# Sensors_v1_0.net
KiCad netlist of a schematic drawn in EAGLE
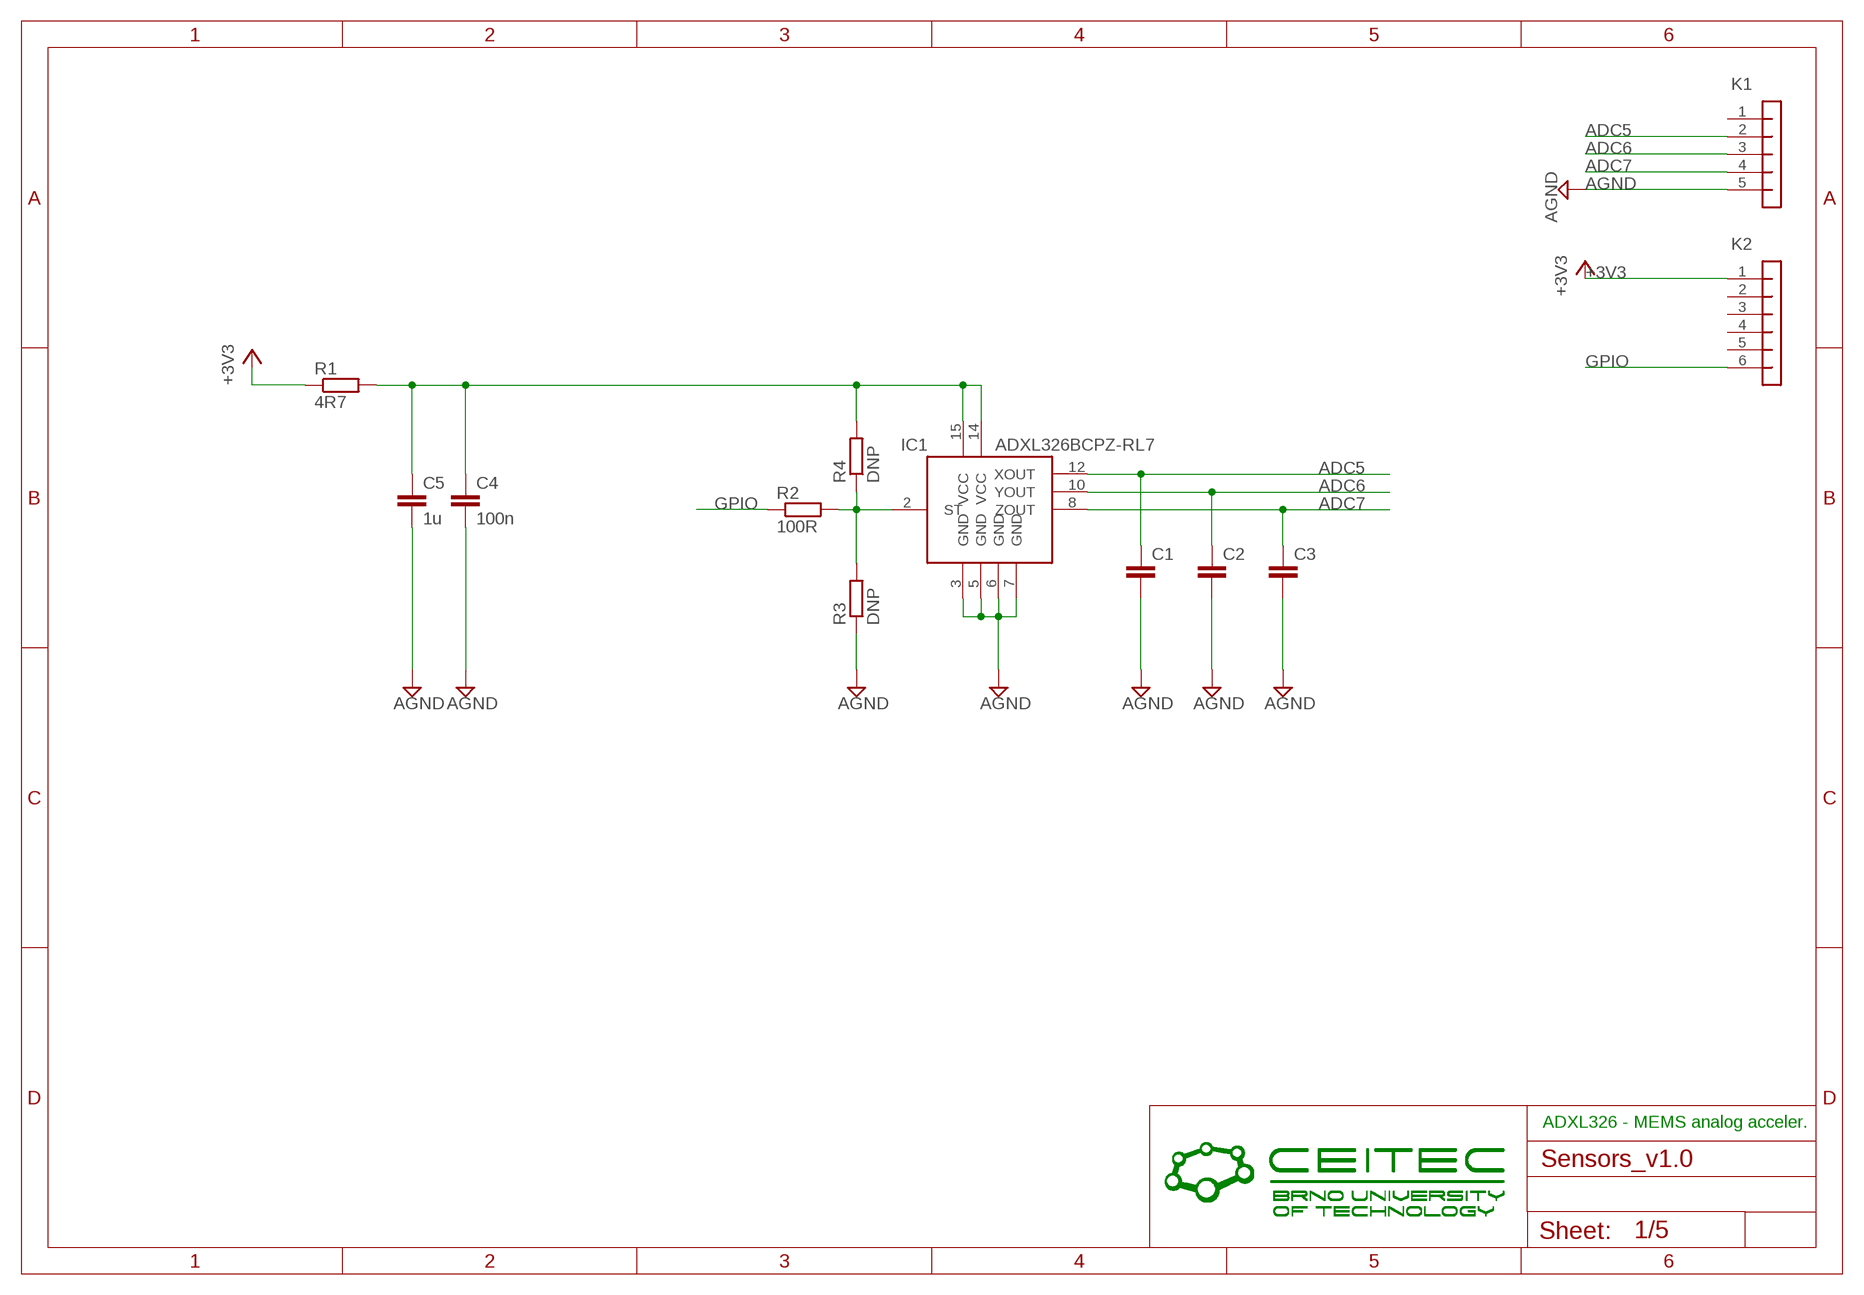
[diagram p0: schematic, sheet 1]
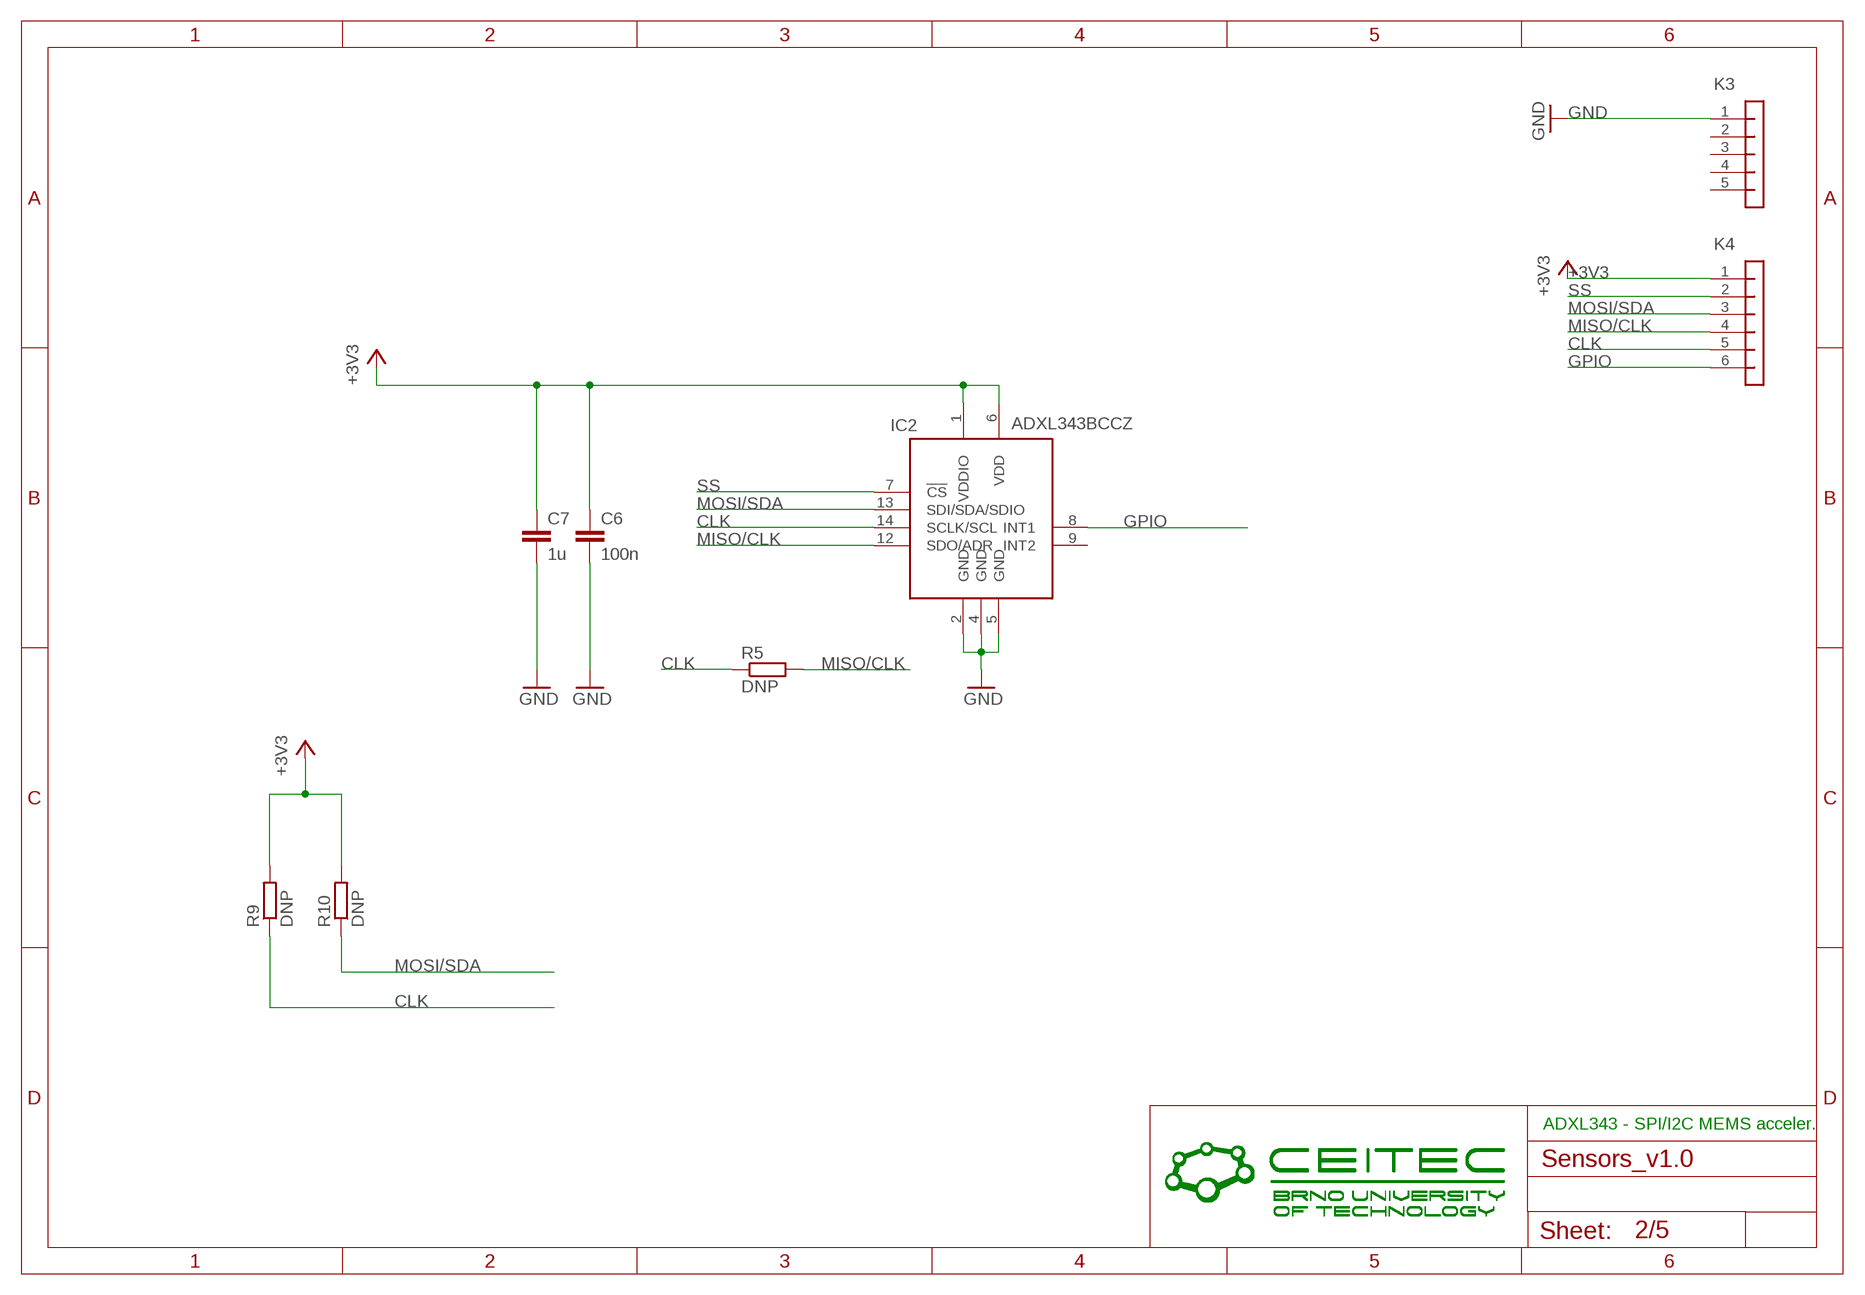
[diagram p1: schematic, sheet 2]
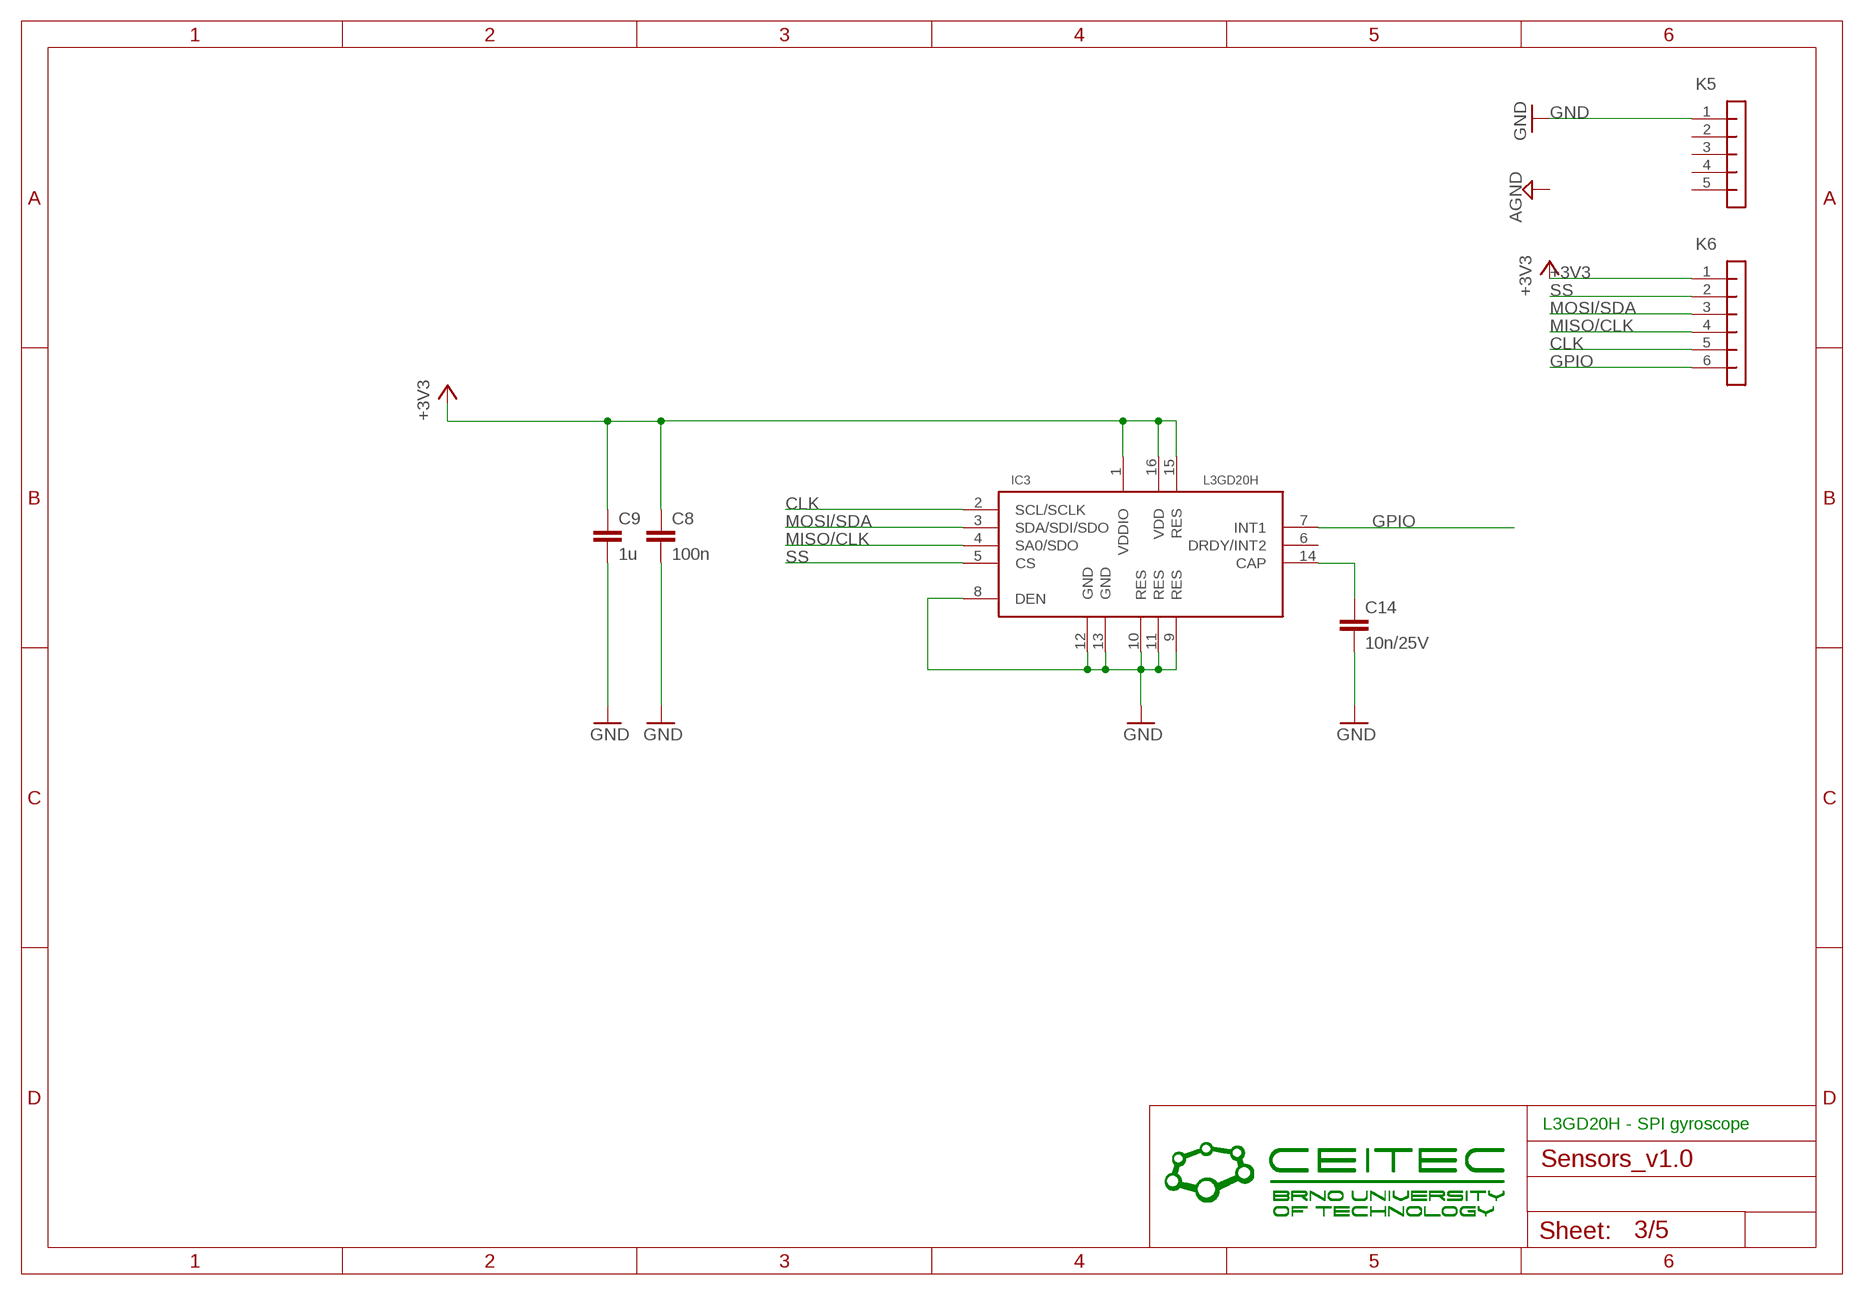
[diagram p2: schematic, sheet 3]
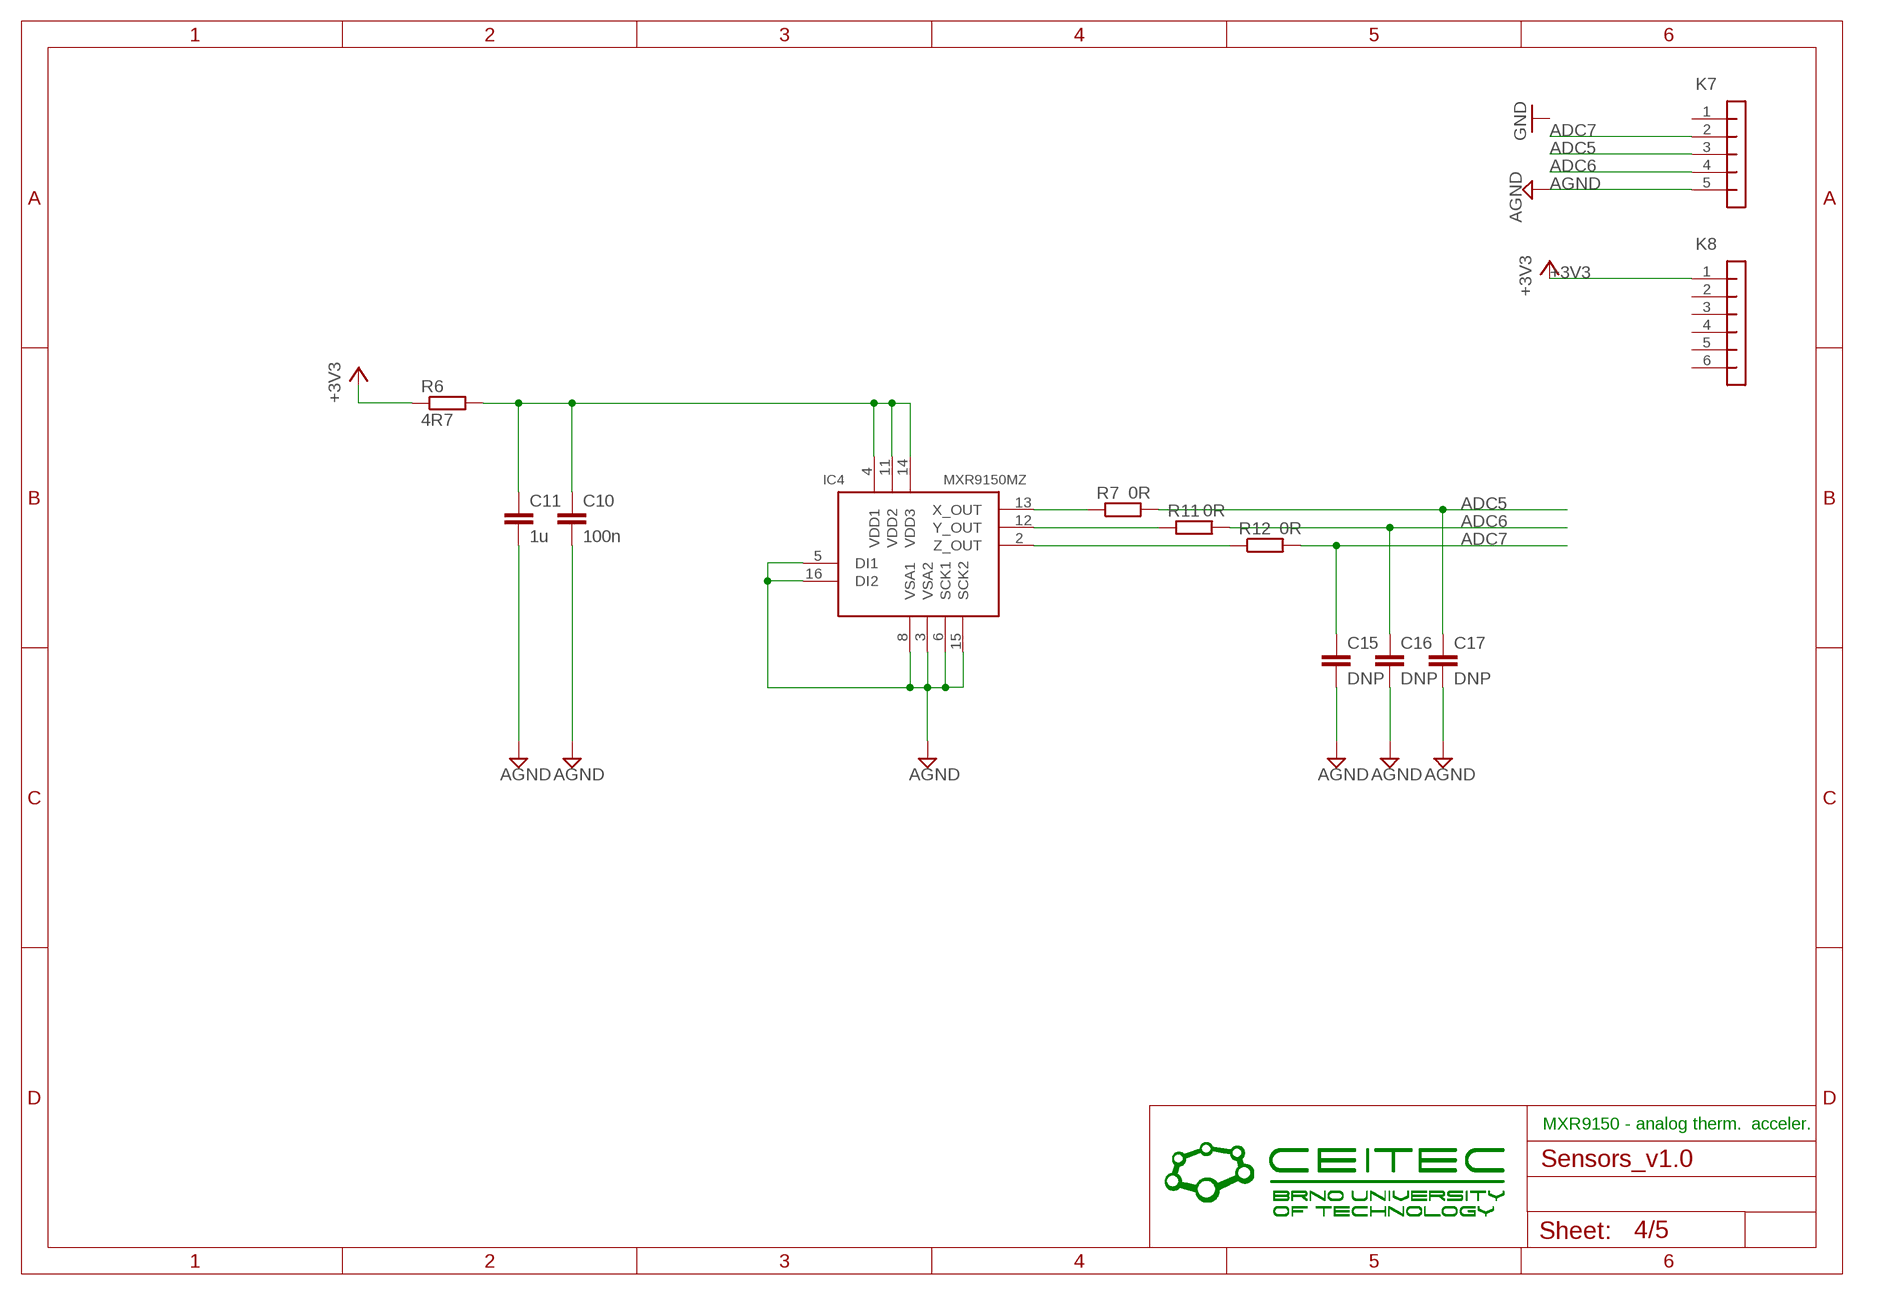
[diagram p3: schematic, sheet 4]
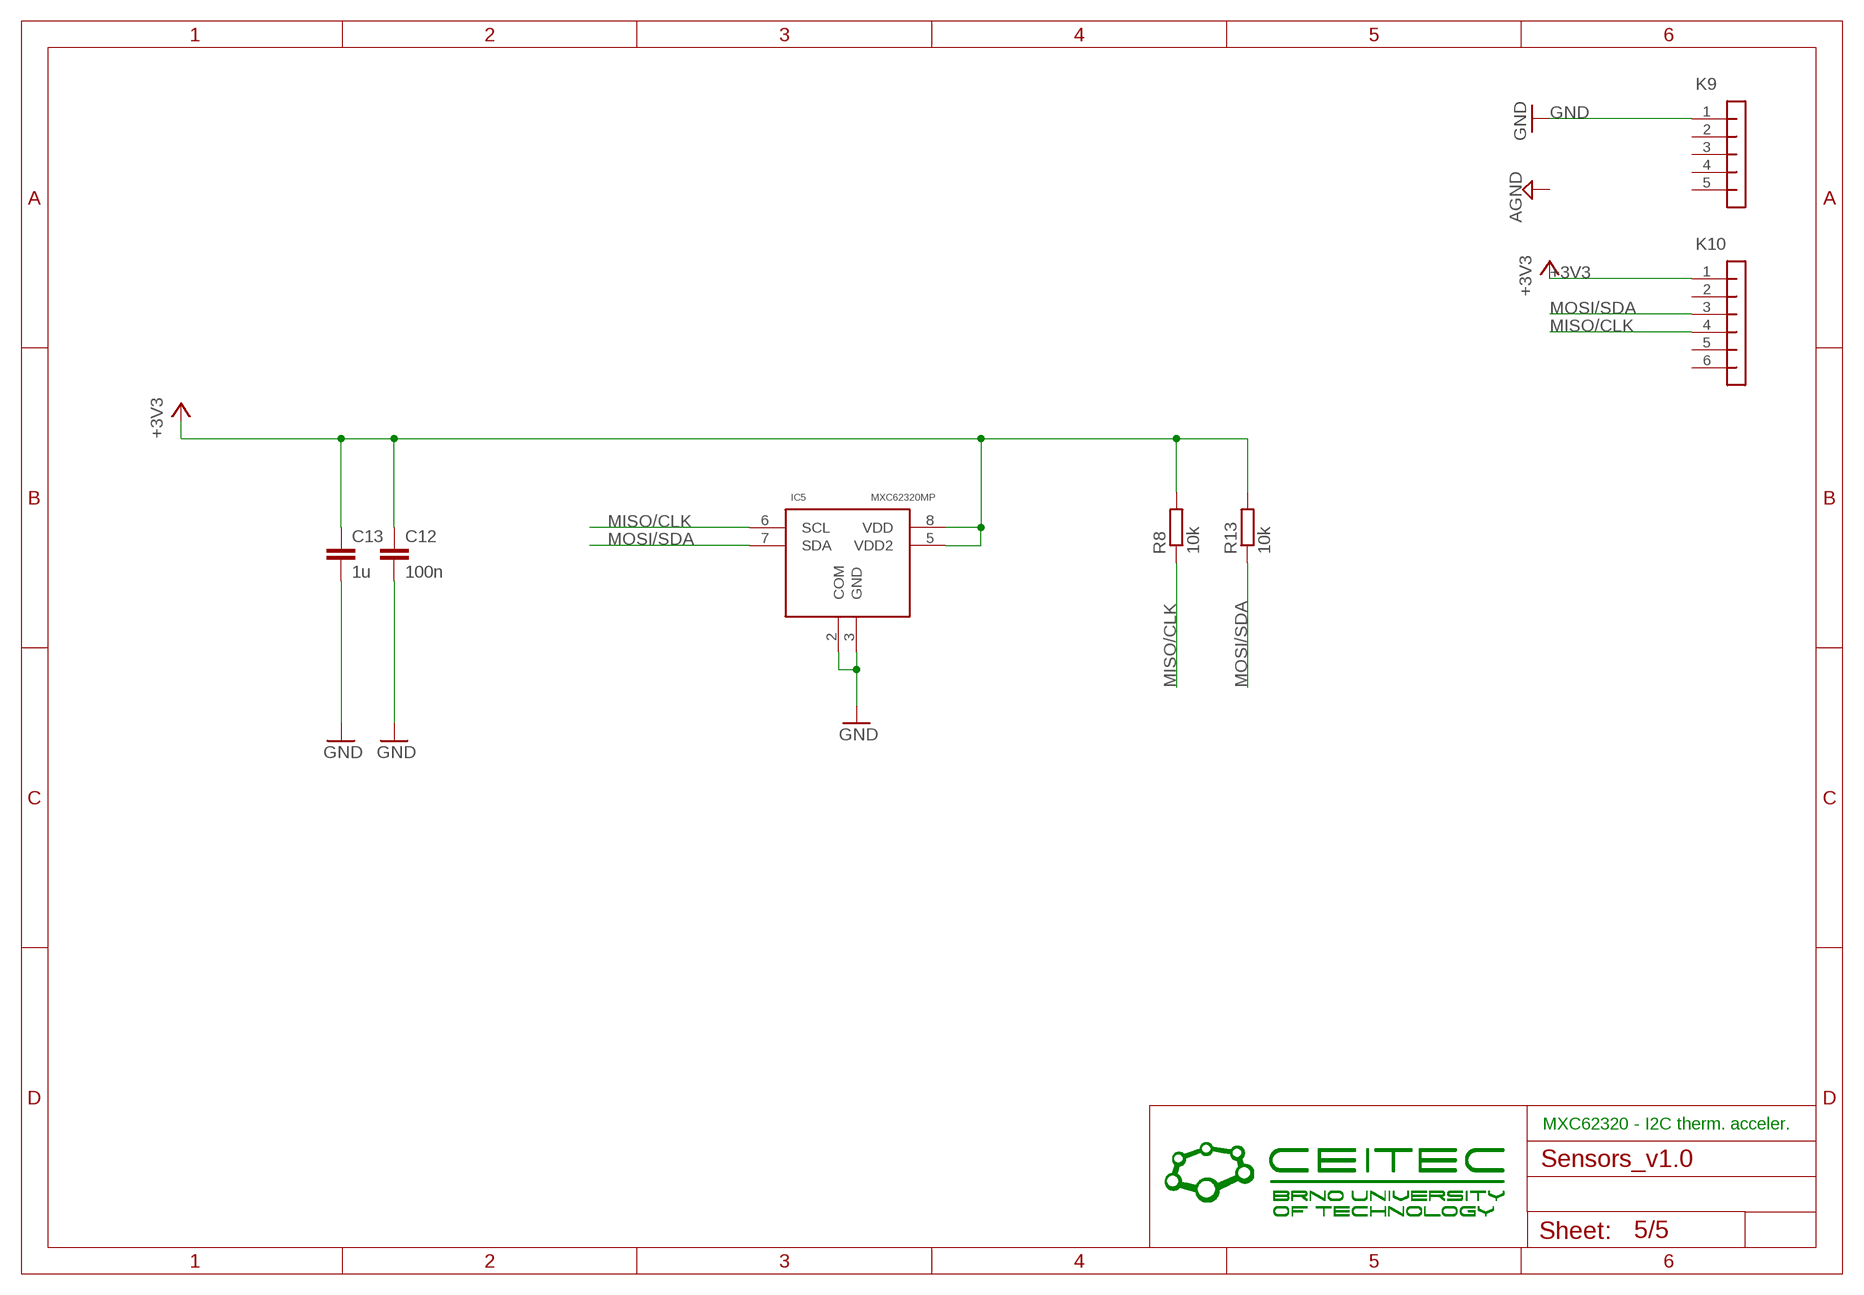
[diagram p4: schematic, sheet 5]

(export (version "E")
  (design (tool "Eeschema 10.0.6"))
  (components
    (comp (ref "C6")
      (value "100n")
      (footprint "eagle-import:C0805K")
      (libsource (lib "eagle-import") (part "C-EUC0805K"))
    )
    (comp (ref "C7")
      (value "1u")
      (footprint "eagle-import:C0805K")
      (libsource (lib "eagle-import") (part "C-EUC0805K"))
    )
    (comp (ref "IC2")
      (value "ADXL343BCCZ")
      (footprint "eagle-import:LGA14(CC-14-1)")
      (libsource (lib "eagle-import") (part "ADXL343BCCZ"))
    )
    (comp (ref "K3")
      (value "PIN_1X5_1.27THT")
      (footprint "eagle-import:PINHEAD_1X5_RM1.27THT")
      (libsource (lib "eagle-import") (part "_dos_PIN_1X5_1.27THT"))
    )
    (comp (ref "K4")
      (value "PIN_1X6_1.27THT")
      (footprint "eagle-import:PINHEAD_1X6_RM1.27THT")
      (libsource (lib "eagle-import") (part "PIN_1X6_1.27THT"))
    )
    (comp (ref "R5")
      (value "DNP")
      (footprint "eagle-import:M0805")
      (libsource (lib "eagle-import") (part "R-EU_M0805"))
    )
    (comp (ref "R9")
      (value "DNP")
      (footprint "eagle-import:M0805")
      (libsource (lib "eagle-import") (part "R-EU_M0805"))
    )
    (comp (ref "R10")
      (value "DNP")
      (footprint "eagle-import:M0805")
      (libsource (lib "eagle-import") (part "R-EU_M0805"))
    )
    (comp (ref "C10")
      (value "100n")
      (footprint "eagle-import:C0805K")
      (libsource (lib "eagle-import") (part "C-EUC0805K"))
    )
    (comp (ref "C11")
      (value "1u")
      (footprint "eagle-import:C0805K")
      (libsource (lib "eagle-import") (part "C-EUC0805K"))
    )
    (comp (ref "C15")
      (value "DNP")
      (footprint "eagle-import:C0805K")
      (libsource (lib "eagle-import") (part "C-EUC0805K"))
    )
    (comp (ref "C16")
      (value "DNP")
      (footprint "eagle-import:C0805K")
      (libsource (lib "eagle-import") (part "C-EUC0805K"))
    )
    (comp (ref "C17")
      (value "DNP")
      (footprint "eagle-import:C0805K")
      (libsource (lib "eagle-import") (part "C-EUC0805K"))
    )
    (comp (ref "IC4")
      (value "MXR9150MZ")
      (footprint "eagle-import:LCC16")
      (libsource (lib "eagle-import") (part "MXR9150MZ"))
    )
    (comp (ref "K7")
      (value "PIN_1X5_1.27THT")
      (footprint "eagle-import:PINHEAD_1X5_RM1.27THT")
      (libsource (lib "eagle-import") (part "_dos_PIN_1X5_1.27THT"))
    )
    (comp (ref "K8")
      (value "PIN_1X6_1.27THT")
      (footprint "eagle-import:PINHEAD_1X6_RM1.27THT")
      (libsource (lib "eagle-import") (part "PIN_1X6_1.27THT"))
    )
    (comp (ref "R6")
      (value "4R7")
      (footprint "eagle-import:M0805")
      (libsource (lib "eagle-import") (part "R-EU_M0805"))
    )
    (comp (ref "R7")
      (value "0R")
      (footprint "eagle-import:M0805")
      (libsource (lib "eagle-import") (part "R-EU_M0805"))
    )
    (comp (ref "R11")
      (value "0R")
      (footprint "eagle-import:M0805")
      (libsource (lib "eagle-import") (part "R-EU_M0805"))
    )
    (comp (ref "R12")
      (value "0R")
      (footprint "eagle-import:M0805")
      (libsource (lib "eagle-import") (part "R-EU_M0805"))
    )
    (comp (ref "C8")
      (value "100n")
      (footprint "eagle-import:C0805K")
      (libsource (lib "eagle-import") (part "C-EUC0805K"))
    )
    (comp (ref "C9")
      (value "1u")
      (footprint "eagle-import:C0805K")
      (libsource (lib "eagle-import") (part "C-EUC0805K"))
    )
    (comp (ref "C14")
      (value "10n/25V")
      (footprint "eagle-import:C0805K")
      (libsource (lib "eagle-import") (part "C-EUC0805K"))
    )
    (comp (ref "IC3")
      (value "L3GD20H")
      (footprint "eagle-import:LGA16L")
      (libsource (lib "eagle-import") (part "L3GD20H"))
    )
    (comp (ref "K5")
      (value "PIN_1X5_1.27THT")
      (footprint "eagle-import:PINHEAD_1X5_RM1.27THT")
      (libsource (lib "eagle-import") (part "_dos_PIN_1X5_1.27THT"))
    )
    (comp (ref "K6")
      (value "PIN_1X6_1.27THT")
      (footprint "eagle-import:PINHEAD_1X6_RM1.27THT")
      (libsource (lib "eagle-import") (part "PIN_1X6_1.27THT"))
    )
    (comp (ref "C12")
      (value "100n")
      (footprint "eagle-import:C0805K")
      (libsource (lib "eagle-import") (part "C-EUC0805K"))
    )
    (comp (ref "C13")
      (value "1u")
      (footprint "eagle-import:C0805K")
      (libsource (lib "eagle-import") (part "C-EUC0805K"))
    )
    (comp (ref "IC5")
      (value "MXC62320MP")
      (footprint "eagle-import:LCC8")
      (libsource (lib "eagle-import") (part "MXC62320MP"))
    )
    (comp (ref "K9")
      (value "PIN_1X5_1.27THT")
      (footprint "eagle-import:PINHEAD_1X5_RM1.27THT")
      (libsource (lib "eagle-import") (part "_dos_PIN_1X5_1.27THT"))
    )
    (comp (ref "K10")
      (value "PIN_1X6_1.27THT")
      (footprint "eagle-import:PINHEAD_1X6_RM1.27THT")
      (libsource (lib "eagle-import") (part "PIN_1X6_1.27THT"))
    )
    (comp (ref "R8")
      (value "10k")
      (footprint "eagle-import:M0805")
      (libsource (lib "eagle-import") (part "R-EU_M0805"))
    )
    (comp (ref "R13")
      (value "10k")
      (footprint "eagle-import:M0805")
      (libsource (lib "eagle-import") (part "R-EU_M0805"))
    )
    (comp (ref "C1")
      (value "C-EUC0805K")
      (footprint "eagle-import:C0805K")
      (libsource (lib "eagle-import") (part "C-EUC0805K"))
    )
    (comp (ref "C2")
      (value "C-EUC0805K")
      (footprint "eagle-import:C0805K")
      (libsource (lib "eagle-import") (part "C-EUC0805K"))
    )
    (comp (ref "C3")
      (value "C-EUC0805K")
      (footprint "eagle-import:C0805K")
      (libsource (lib "eagle-import") (part "C-EUC0805K"))
    )
    (comp (ref "C4")
      (value "100n")
      (footprint "eagle-import:C0805K")
      (libsource (lib "eagle-import") (part "C-EUC0805K"))
    )
    (comp (ref "C5")
      (value "1u")
      (footprint "eagle-import:C0805K")
      (libsource (lib "eagle-import") (part "C-EUC0805K"))
    )
    (comp (ref "IC1")
      (value "ADXL326BCPZ-RL7")
      (footprint "eagle-import:LFCSP-LQ-16")
      (libsource (lib "eagle-import") (part "ADXL326"))
    )
    (comp (ref "K1")
      (value "PIN_1X5_1.27THT")
      (footprint "eagle-import:PINHEAD_1X5_RM1.27THT")
      (libsource (lib "eagle-import") (part "_dos_PIN_1X5_1.27THT"))
    )
    (comp (ref "K2")
      (value "PIN_1X6_1.27THT")
      (footprint "eagle-import:PINHEAD_1X6_RM1.27THT")
      (libsource (lib "eagle-import") (part "PIN_1X6_1.27THT"))
    )
    (comp (ref "R1")
      (value "4R7")
      (footprint "eagle-import:M0805")
      (libsource (lib "eagle-import") (part "R-EU_M0805"))
    )
    (comp (ref "R2")
      (value "100R")
      (footprint "eagle-import:M0805")
      (libsource (lib "eagle-import") (part "R-EU_M0805"))
    )
    (comp (ref "R3")
      (value "DNP")
      (footprint "eagle-import:M0805")
      (libsource (lib "eagle-import") (part "R-EU_M0805"))
    )
    (comp (ref "R4")
      (value "DNP")
      (footprint "eagle-import:M0805")
      (libsource (lib "eagle-import") (part "R-EU_M0805"))
    )
  )
  (nets
    (net (code "1") (name "+3V3") (class "Default")
      (node (ref "C12") (pin "1") (pinfunction "1_1") (pintype "passive"))
      (node (ref "C13") (pin "1") (pinfunction "1_1") (pintype "passive"))
      (node (ref "C6") (pin "1") (pinfunction "1_1") (pintype "passive"))
      (node (ref "C7") (pin "1") (pinfunction "1_1") (pintype "passive"))
      (node (ref "C8") (pin "1") (pinfunction "1_1") (pintype "passive"))
      (node (ref "C9") (pin "1") (pinfunction "1_1") (pintype "passive"))
      (node (ref "IC2") (pin "1") (pinfunction "VDDIO_1") (pintype "bidirectional"))
      (node (ref "IC2") (pin "6") (pinfunction "VDD_6") (pintype "bidirectional"))
      (node (ref "IC3") (pin "1") (pinfunction "VDDIO_1") (pintype "bidirectional"))
      (node (ref "IC3") (pin "15") (pinfunction "RES_15") (pintype "bidirectional"))
      (node (ref "IC3") (pin "16") (pinfunction "VDD_16") (pintype "bidirectional"))
      (node (ref "IC5") (pin "5") (pinfunction "VDD2_5") (pintype "bidirectional"))
      (node (ref "IC5") (pin "8") (pinfunction "VDD_8") (pintype "bidirectional"))
      (node (ref "K10") (pin "1") (pinfunction "P$1_1") (pintype "bidirectional"))
      (node (ref "K2") (pin "1") (pinfunction "P$1_1") (pintype "bidirectional"))
      (node (ref "K4") (pin "1") (pinfunction "P$1_1") (pintype "bidirectional"))
      (node (ref "K6") (pin "1") (pinfunction "P$1_1") (pintype "bidirectional"))
      (node (ref "K8") (pin "1") (pinfunction "P$1_1") (pintype "bidirectional"))
      (node (ref "R1") (pin "1") (pinfunction "1_1") (pintype "passive"))
      (node (ref "R10") (pin "2") (pinfunction "2_2") (pintype "passive"))
      (node (ref "R13") (pin "2") (pinfunction "2_2") (pintype "passive"))
      (node (ref "R6") (pin "1") (pinfunction "1_1") (pintype "passive"))
      (node (ref "R8") (pin "2") (pinfunction "2_2") (pintype "passive"))
      (node (ref "R9") (pin "2") (pinfunction "2_2") (pintype "passive"))
    )
    (net (code "2") (name "ADC5") (class "Default")
      (node (ref "C1") (pin "1") (pinfunction "1_1") (pintype "passive"))
      (node (ref "C17") (pin "1") (pinfunction "1_1") (pintype "passive"))
      (node (ref "IC1") (pin "12") (pinfunction "XOUT_12") (pintype "bidirectional"))
      (node (ref "K1") (pin "2") (pinfunction "P$2_2") (pintype "bidirectional"))
      (node (ref "K7") (pin "3") (pinfunction "P$3_3") (pintype "bidirectional"))
      (node (ref "R7") (pin "2") (pinfunction "2_2") (pintype "passive"))
    )
    (net (code "3") (name "ADC6") (class "Default")
      (node (ref "C16") (pin "1") (pinfunction "1_1") (pintype "passive"))
      (node (ref "C2") (pin "1") (pinfunction "1_1") (pintype "passive"))
      (node (ref "IC1") (pin "10") (pinfunction "YOUT_10") (pintype "bidirectional"))
      (node (ref "K1") (pin "3") (pinfunction "P$3_3") (pintype "bidirectional"))
      (node (ref "K7") (pin "4") (pinfunction "P$4_4") (pintype "bidirectional"))
      (node (ref "R11") (pin "2") (pinfunction "2_2") (pintype "passive"))
    )
    (net (code "4") (name "ADC7") (class "Default")
      (node (ref "C15") (pin "1") (pinfunction "1_1") (pintype "passive"))
      (node (ref "C3") (pin "1") (pinfunction "1_1") (pintype "passive"))
      (node (ref "IC1") (pin "8") (pinfunction "ZOUT_8") (pintype "bidirectional"))
      (node (ref "K1") (pin "4") (pinfunction "P$4_4") (pintype "bidirectional"))
      (node (ref "K7") (pin "2") (pinfunction "P$2_2") (pintype "bidirectional"))
      (node (ref "R12") (pin "2") (pinfunction "2_2") (pintype "passive"))
    )
    (net (code "5") (name "AGND") (class "Default")
      (node (ref "C1") (pin "2") (pinfunction "2_2") (pintype "passive"))
      (node (ref "C10") (pin "2") (pinfunction "2_2") (pintype "passive"))
      (node (ref "C11") (pin "2") (pinfunction "2_2") (pintype "passive"))
      (node (ref "C15") (pin "2") (pinfunction "2_2") (pintype "passive"))
      (node (ref "C16") (pin "2") (pinfunction "2_2") (pintype "passive"))
      (node (ref "C17") (pin "2") (pinfunction "2_2") (pintype "passive"))
      (node (ref "C2") (pin "2") (pinfunction "2_2") (pintype "passive"))
      (node (ref "C3") (pin "2") (pinfunction "2_2") (pintype "passive"))
      (node (ref "C4") (pin "2") (pinfunction "2_2") (pintype "passive"))
      (node (ref "C5") (pin "2") (pinfunction "2_2") (pintype "passive"))
      (node (ref "IC1") (pin "3") (pinfunction "GND_3") (pintype "bidirectional"))
      (node (ref "IC1") (pin "5") (pinfunction "GND_5") (pintype "bidirectional"))
      (node (ref "IC1") (pin "6") (pinfunction "GND_6") (pintype "bidirectional"))
      (node (ref "IC1") (pin "7") (pinfunction "GND_7") (pintype "bidirectional"))
      (node (ref "IC4") (pin "15") (pinfunction "SCK2_15") (pintype "bidirectional"))
      (node (ref "IC4") (pin "16") (pinfunction "DI2_16") (pintype "bidirectional"))
      (node (ref "IC4") (pin "3") (pinfunction "VSA2_3") (pintype "bidirectional"))
      (node (ref "IC4") (pin "5") (pinfunction "DI1_5") (pintype "bidirectional"))
      (node (ref "IC4") (pin "6") (pinfunction "SCK1_6") (pintype "bidirectional"))
      (node (ref "IC4") (pin "8") (pinfunction "VSA1_8") (pintype "bidirectional"))
      (node (ref "K1") (pin "5") (pinfunction "P$5_5") (pintype "bidirectional"))
      (node (ref "K7") (pin "5") (pinfunction "P$5_5") (pintype "bidirectional"))
      (node (ref "R3") (pin "1") (pinfunction "1_1") (pintype "passive"))
    )
    (net (code "6") (name "CLK") (class "Default")
      (node (ref "IC2") (pin "14") (pinfunction "SCLK/SCL_14") (pintype "bidirectional"))
      (node (ref "IC3") (pin "2") (pinfunction "SCL/SCLK_2") (pintype "bidirectional"))
      (node (ref "K4") (pin "5") (pinfunction "P$5_5") (pintype "bidirectional"))
      (node (ref "K6") (pin "5") (pinfunction "P$5_5") (pintype "bidirectional"))
      (node (ref "R5") (pin "1") (pinfunction "1_1") (pintype "passive"))
      (node (ref "R9") (pin "1") (pinfunction "1_1") (pintype "passive"))
    )
    (net (code "7") (name "GND") (class "Default")
      (node (ref "C12") (pin "2") (pinfunction "2_2") (pintype "passive"))
      (node (ref "C13") (pin "2") (pinfunction "2_2") (pintype "passive"))
      (node (ref "C14") (pin "2") (pinfunction "2_2") (pintype "passive"))
      (node (ref "C6") (pin "2") (pinfunction "2_2") (pintype "passive"))
      (node (ref "C7") (pin "2") (pinfunction "2_2") (pintype "passive"))
      (node (ref "C8") (pin "2") (pinfunction "2_2") (pintype "passive"))
      (node (ref "C9") (pin "2") (pinfunction "2_2") (pintype "passive"))
      (node (ref "IC2") (pin "2") (pinfunction "GND_2") (pintype "bidirectional"))
      (node (ref "IC2") (pin "4") (pinfunction "GND_4") (pintype "bidirectional"))
      (node (ref "IC2") (pin "5") (pinfunction "GND_5") (pintype "bidirectional"))
      (node (ref "IC3") (pin "10") (pinfunction "RES_10") (pintype "bidirectional"))
      (node (ref "IC3") (pin "11") (pinfunction "RES_11") (pintype "bidirectional"))
      (node (ref "IC3") (pin "12") (pinfunction "GND_12") (pintype "bidirectional"))
      (node (ref "IC3") (pin "13") (pinfunction "GND_13") (pintype "bidirectional"))
      (node (ref "IC3") (pin "8") (pinfunction "DEN_8") (pintype "bidirectional"))
      (node (ref "IC3") (pin "9") (pinfunction "RES_9") (pintype "bidirectional"))
      (node (ref "IC5") (pin "2") (pinfunction "COM_2") (pintype "bidirectional"))
      (node (ref "IC5") (pin "3") (pinfunction "GND_3") (pintype "bidirectional"))
      (node (ref "K3") (pin "1") (pinfunction "P$1_1") (pintype "bidirectional"))
      (node (ref "K5") (pin "1") (pinfunction "P$1_1") (pintype "bidirectional"))
      (node (ref "K9") (pin "1") (pinfunction "P$1_1") (pintype "bidirectional"))
    )
    (net (code "8") (name "GPIO") (class "Default")
      (node (ref "IC2") (pin "8") (pinfunction "INT1_8") (pintype "bidirectional"))
      (node (ref "IC3") (pin "7") (pinfunction "INT1_7") (pintype "bidirectional"))
      (node (ref "K2") (pin "6") (pinfunction "P$6_6") (pintype "bidirectional"))
      (node (ref "K4") (pin "6") (pinfunction "P$6_6") (pintype "bidirectional"))
      (node (ref "K6") (pin "6") (pinfunction "P$6_6") (pintype "bidirectional"))
      (node (ref "R2") (pin "1") (pinfunction "1_1") (pintype "passive"))
    )
    (net (code "9") (name "MISO{slash}CLK") (class "Default")
      (node (ref "IC2") (pin "12") (pinfunction "SDO/ADR_12") (pintype "bidirectional"))
      (node (ref "IC3") (pin "4") (pinfunction "SA0/SDO_4") (pintype "bidirectional"))
      (node (ref "IC5") (pin "6") (pinfunction "SCL_6") (pintype "bidirectional"))
      (node (ref "K10") (pin "4") (pinfunction "P$4_4") (pintype "bidirectional"))
      (node (ref "K4") (pin "4") (pinfunction "P$4_4") (pintype "bidirectional"))
      (node (ref "K6") (pin "4") (pinfunction "P$4_4") (pintype "bidirectional"))
      (node (ref "R5") (pin "2") (pinfunction "2_2") (pintype "passive"))
      (node (ref "R8") (pin "1") (pinfunction "1_1") (pintype "passive"))
    )
    (net (code "10") (name "MOSI{slash}SDA") (class "Default")
      (node (ref "IC2") (pin "13") (pinfunction "SDI/SDA/SDIO_13") (pintype "bidirectional"))
      (node (ref "IC3") (pin "3") (pinfunction "SDA/SDI/SDO_3") (pintype "bidirectional"))
      (node (ref "IC5") (pin "7") (pinfunction "SDA_7") (pintype "bidirectional"))
      (node (ref "K10") (pin "3") (pinfunction "P$3_3") (pintype "bidirectional"))
      (node (ref "K4") (pin "3") (pinfunction "P$3_3") (pintype "bidirectional"))
      (node (ref "K6") (pin "3") (pinfunction "P$3_3") (pintype "bidirectional"))
      (node (ref "R10") (pin "1") (pinfunction "1_1") (pintype "passive"))
      (node (ref "R13") (pin "1") (pinfunction "1_1") (pintype "passive"))
    )
    (net (code "11") (name "Net-(C4-Pad1)") (class "Default")
      (node (ref "C4") (pin "1") (pinfunction "1_1") (pintype "passive"))
      (node (ref "C5") (pin "1") (pinfunction "1_1") (pintype "passive"))
      (node (ref "IC1") (pin "14") (pinfunction "VCC_14") (pintype "bidirectional"))
      (node (ref "IC1") (pin "15") (pinfunction "VCC_15") (pintype "bidirectional"))
      (node (ref "R1") (pin "2") (pinfunction "2_2") (pintype "passive"))
      (node (ref "R4") (pin "2") (pinfunction "2_2") (pintype "passive"))
    )
    (net (code "12") (name "Net-(IC1-ST)") (class "Default")
      (node (ref "IC1") (pin "2") (pinfunction "ST_2") (pintype "bidirectional"))
      (node (ref "R2") (pin "2") (pinfunction "2_2") (pintype "passive"))
      (node (ref "R3") (pin "2") (pinfunction "2_2") (pintype "passive"))
      (node (ref "R4") (pin "1") (pinfunction "1_1") (pintype "passive"))
    )
    (net (code "13") (name "Net-(IC3-CAP)") (class "Default")
      (node (ref "C14") (pin "1") (pinfunction "1_1") (pintype "passive"))
      (node (ref "IC3") (pin "14") (pinfunction "CAP_14") (pintype "bidirectional"))
    )
    (net (code "14") (name "Net-(IC4-VDD1)") (class "Default")
      (node (ref "C10") (pin "1") (pinfunction "1_1") (pintype "passive"))
      (node (ref "C11") (pin "1") (pinfunction "1_1") (pintype "passive"))
      (node (ref "IC4") (pin "11") (pinfunction "VDD2_11") (pintype "bidirectional"))
      (node (ref "IC4") (pin "14") (pinfunction "VDD3_14") (pintype "bidirectional"))
      (node (ref "IC4") (pin "4") (pinfunction "VDD1_4") (pintype "bidirectional"))
      (node (ref "R6") (pin "2") (pinfunction "2_2") (pintype "passive"))
    )
    (net (code "15") (name "Net-(IC4-X_OUT)") (class "Default")
      (node (ref "IC4") (pin "13") (pinfunction "X_OUT_13") (pintype "bidirectional"))
      (node (ref "R7") (pin "1") (pinfunction "1_1") (pintype "passive"))
    )
    (net (code "16") (name "Net-(IC4-Y_OUT)") (class "Default")
      (node (ref "IC4") (pin "12") (pinfunction "Y_OUT_12") (pintype "bidirectional"))
      (node (ref "R11") (pin "1") (pinfunction "1_1") (pintype "passive"))
    )
    (net (code "17") (name "Net-(IC4-Z_OUT)") (class "Default")
      (node (ref "IC4") (pin "2") (pinfunction "Z_OUT_2") (pintype "bidirectional"))
      (node (ref "R12") (pin "1") (pinfunction "1_1") (pintype "passive"))
    )
    (net (code "18") (name "SS") (class "Default")
      (node (ref "IC2") (pin "7") (pinfunction "~{CS}_7") (pintype "bidirectional"))
      (node (ref "IC3") (pin "5") (pinfunction "CS_5") (pintype "bidirectional"))
      (node (ref "K4") (pin "2") (pinfunction "P$2_2") (pintype "bidirectional"))
      (node (ref "K6") (pin "2") (pinfunction "P$2_2") (pintype "bidirectional"))
    )
    (net (code "19") (name "unconnected-(IC2-INT2-Pad9)") (class "Default")
      (node (ref "IC2") (pin "9") (pinfunction "INT2_9") (pintype "bidirectional"))
    )
    (net (code "20") (name "unconnected-(IC3-DRDY{slash}INT2-Pad6)") (class "Default")
      (node (ref "IC3") (pin "6") (pinfunction "DRDY/INT2_6") (pintype "bidirectional"))
    )
    (net (code "21") (name "unconnected-(K1-P$1-Pad1)") (class "Default")
      (node (ref "K1") (pin "1") (pinfunction "P$1_1") (pintype "bidirectional"))
    )
    (net (code "22") (name "unconnected-(K2-P$2-Pad2)") (class "Default")
      (node (ref "K2") (pin "2") (pinfunction "P$2_2") (pintype "bidirectional"))
    )
    (net (code "23") (name "unconnected-(K2-P$3-Pad3)") (class "Default")
      (node (ref "K2") (pin "3") (pinfunction "P$3_3") (pintype "bidirectional"))
    )
    (net (code "24") (name "unconnected-(K2-P$4-Pad4)") (class "Default")
      (node (ref "K2") (pin "4") (pinfunction "P$4_4") (pintype "bidirectional"))
    )
    (net (code "25") (name "unconnected-(K2-P$5-Pad5)") (class "Default")
      (node (ref "K2") (pin "5") (pinfunction "P$5_5") (pintype "bidirectional"))
    )
    (net (code "26") (name "unconnected-(K3-P$2-Pad2)") (class "Default")
      (node (ref "K3") (pin "2") (pinfunction "P$2_2") (pintype "bidirectional"))
    )
    (net (code "27") (name "unconnected-(K3-P$3-Pad3)") (class "Default")
      (node (ref "K3") (pin "3") (pinfunction "P$3_3") (pintype "bidirectional"))
    )
    (net (code "28") (name "unconnected-(K3-P$4-Pad4)") (class "Default")
      (node (ref "K3") (pin "4") (pinfunction "P$4_4") (pintype "bidirectional"))
    )
    (net (code "29") (name "unconnected-(K3-P$5-Pad5)") (class "Default")
      (node (ref "K3") (pin "5") (pinfunction "P$5_5") (pintype "bidirectional"))
    )
    (net (code "30") (name "unconnected-(K5-P$2-Pad2)") (class "Default")
      (node (ref "K5") (pin "2") (pinfunction "P$2_2") (pintype "bidirectional"))
    )
    (net (code "31") (name "unconnected-(K5-P$3-Pad3)") (class "Default")
      (node (ref "K5") (pin "3") (pinfunction "P$3_3") (pintype "bidirectional"))
    )
    (net (code "32") (name "unconnected-(K5-P$4-Pad4)") (class "Default")
      (node (ref "K5") (pin "4") (pinfunction "P$4_4") (pintype "bidirectional"))
    )
    (net (code "33") (name "unconnected-(K5-P$5-Pad5)") (class "Default")
      (node (ref "K5") (pin "5") (pinfunction "P$5_5") (pintype "bidirectional"))
    )
    (net (code "34") (name "unconnected-(K7-P$1-Pad1)") (class "Default")
      (node (ref "K7") (pin "1") (pinfunction "P$1_1") (pintype "bidirectional"))
    )
    (net (code "35") (name "unconnected-(K8-P$2-Pad2)") (class "Default")
      (node (ref "K8") (pin "2") (pinfunction "P$2_2") (pintype "bidirectional"))
    )
    (net (code "36") (name "unconnected-(K8-P$3-Pad3)") (class "Default")
      (node (ref "K8") (pin "3") (pinfunction "P$3_3") (pintype "bidirectional"))
    )
    (net (code "37") (name "unconnected-(K8-P$4-Pad4)") (class "Default")
      (node (ref "K8") (pin "4") (pinfunction "P$4_4") (pintype "bidirectional"))
    )
    (net (code "38") (name "unconnected-(K8-P$5-Pad5)") (class "Default")
      (node (ref "K8") (pin "5") (pinfunction "P$5_5") (pintype "bidirectional"))
    )
    (net (code "39") (name "unconnected-(K8-P$6-Pad6)") (class "Default")
      (node (ref "K8") (pin "6") (pinfunction "P$6_6") (pintype "bidirectional"))
    )
    (net (code "40") (name "unconnected-(K9-P$2-Pad2)") (class "Default")
      (node (ref "K9") (pin "2") (pinfunction "P$2_2") (pintype "bidirectional"))
    )
    (net (code "41") (name "unconnected-(K9-P$3-Pad3)") (class "Default")
      (node (ref "K9") (pin "3") (pinfunction "P$3_3") (pintype "bidirectional"))
    )
    (net (code "42") (name "unconnected-(K9-P$4-Pad4)") (class "Default")
      (node (ref "K9") (pin "4") (pinfunction "P$4_4") (pintype "bidirectional"))
    )
    (net (code "43") (name "unconnected-(K9-P$5-Pad5)") (class "Default")
      (node (ref "K9") (pin "5") (pinfunction "P$5_5") (pintype "bidirectional"))
    )
    (net (code "44") (name "unconnected-(K10-P$2-Pad2)") (class "Default")
      (node (ref "K10") (pin "2") (pinfunction "P$2_2") (pintype "bidirectional"))
    )
    (net (code "45") (name "unconnected-(K10-P$5-Pad5)") (class "Default")
      (node (ref "K10") (pin "5") (pinfunction "P$5_5") (pintype "bidirectional"))
    )
    (net (code "46") (name "unconnected-(K10-P$6-Pad6)") (class "Default")
      (node (ref "K10") (pin "6") (pinfunction "P$6_6") (pintype "bidirectional"))
    )
  )
)
